# USB_to_UART.net
KiCad netlist of a schematic drawn in Altium Designer
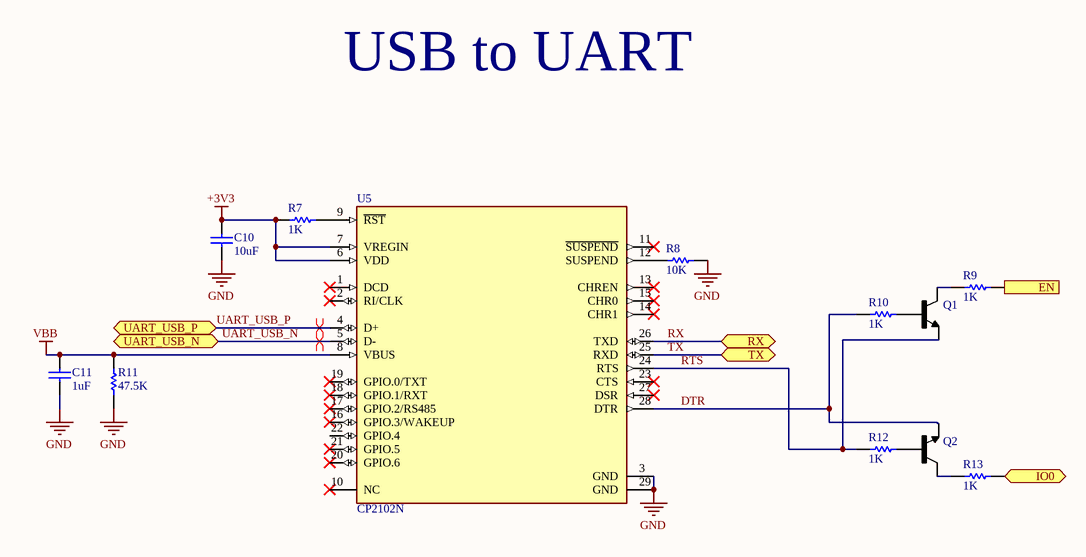
[diagram p0: USB to UART.SchDoc]

(export (version "E")
  (design (tool "Eeschema 10.0.6"))
  (components
    (comp (ref "C10") (value "10uF") (footprint "C0402") (libsource (lib "Schlib1") (part "Cap")))
    (comp (ref "C11") (value "1uF") (footprint "C0402") (libsource (lib "Schlib1") (part "Cap")))
    (comp (ref "Q1") (value "Transistor") (footprint "Transistor") (libsource (lib "") (part "Transistor_1")))
    (comp (ref "Q2")
      (value "Transistor")
      (footprint "Transistor")
      (libsource (lib "Schlib1") (part "Transistor"))
    )
    (comp (ref "R7") (value "1K") (footprint "R0402") (libsource (lib "Schlib1") (part "Res")))
    (comp (ref "R8") (value "10K") (footprint "R0402") (libsource (lib "Schlib1") (part "Res")))
    (comp (ref "R9") (value "1K") (footprint "R0402") (libsource (lib "Schlib1") (part "Res")))
    (comp (ref "R10") (value "1K") (footprint "R0402") (libsource (lib "Schlib1") (part "Res")))
    (comp (ref "R11") (value "47.5K") (footprint "R0402") (libsource (lib "Schlib1") (part "Res")))
    (comp (ref "R12") (value "1K") (footprint "R0402") (libsource (lib "Schlib1") (part "Res")))
    (comp (ref "R13") (value "1K") (footprint "R0402") (libsource (lib "Schlib1") (part "Res")))
    (comp (ref "U5")
      (value "CP2102N")
      (footprint "QFN28")
      (description "USB Bridge, USB to UART USB 2.0 UART Interface 28-QFN (5x5)")
      (libsource (lib "Schlib1") (part "CP2102N"))
    )
  )
  (nets
    (net (code "1") (name "+3V3") (class "Default")
      (node (ref "C10") (pin "02") (pinfunction "-_02") (pintype "passive"))
      (node (ref "R7") (pin "02") (pinfunction "02_02") (pintype "passive"))
      (node (ref "U5") (pin "6") (pinfunction "VDD_6") (pintype "input"))
      (node (ref "U5") (pin "7") (pinfunction "VREGIN_7") (pintype "input"))
    )
    (net (code "2") (name "/DTR") (class "Default")
      (node (ref "Q2") (pin "2") (pinfunction "E_2") (pintype "passive"))
      (node (ref "R10") (pin "02") (pinfunction "02_02") (pintype "passive"))
      (node (ref "U5") (pin "28") (pinfunction "DTR_28") (pintype "output"))
    )
    (net (code "3") (name "/EN") (class "Default")
      (node (ref "R9") (pin "01") (pinfunction "01_01") (pintype "passive"))
    )
    (net (code "4") (name "/IO0") (class "Default")
      (node (ref "R13") (pin "01") (pinfunction "01_01") (pintype "passive"))
    )
    (net (code "5") (name "/RTS") (class "Default")
      (node (ref "Q1") (pin "2") (pinfunction "E_2") (pintype "passive"))
      (node (ref "R12") (pin "02") (pinfunction "02_02") (pintype "passive"))
      (node (ref "U5") (pin "24") (pinfunction "RTS_24") (pintype "output"))
    )
    (net (code "6") (name "/RX") (class "Default")
      (node (ref "U5") (pin "26") (pinfunction "TXD_26") (pintype "bidirectional"))
    )
    (net (code "7") (name "/TX") (class "Default")
      (node (ref "U5") (pin "25") (pinfunction "RXD_25") (pintype "bidirectional"))
    )
    (net (code "8") (name "/UART_USB_N") (class "Default")
      (node (ref "U5") (pin "5") (pinfunction "D-_5") (pintype "bidirectional"))
    )
    (net (code "9") (name "/UART_USB_P") (class "Default")
      (node (ref "U5") (pin "4") (pinfunction "D+_4") (pintype "bidirectional"))
    )
    (net (code "10") (name "GND") (class "Default")
      (node (ref "C10") (pin "01") (pinfunction "+_01") (pintype "passive"))
      (node (ref "C11") (pin "01") (pinfunction "+_01") (pintype "passive"))
      (node (ref "R11") (pin "01") (pinfunction "01_01") (pintype "passive"))
      (node (ref "R8") (pin "01") (pinfunction "01_01") (pintype "passive"))
      (node (ref "U5") (pin "29") (pinfunction "GND_29") (pintype "power_in"))
      (node (ref "U5") (pin "3") (pinfunction "GND_3") (pintype "power_in"))
    )
    (net (code "11") (name "Net-(Q1-B)") (class "Default")
      (node (ref "Q1") (pin "1") (pinfunction "B_1") (pintype "passive"))
      (node (ref "R10") (pin "01") (pinfunction "01_01") (pintype "passive"))
    )
    (net (code "12") (name "Net-(Q1-C)") (class "Default")
      (node (ref "Q1") (pin "3") (pinfunction "C_3") (pintype "passive"))
      (node (ref "R9") (pin "02") (pinfunction "02_02") (pintype "passive"))
    )
    (net (code "13") (name "Net-(Q2-B)") (class "Default")
      (node (ref "Q2") (pin "1") (pinfunction "B_1") (pintype "passive"))
      (node (ref "R12") (pin "01") (pinfunction "01_01") (pintype "passive"))
    )
    (net (code "14") (name "Net-(Q2-C)") (class "Default")
      (node (ref "Q2") (pin "3") (pinfunction "C_3") (pintype "passive"))
      (node (ref "R13") (pin "02") (pinfunction "02_02") (pintype "passive"))
    )
    (net (code "15") (name "Net-(U5-SUSPEND)") (class "Default")
      (node (ref "R8") (pin "02") (pinfunction "02_02") (pintype "passive"))
      (node (ref "U5") (pin "12") (pinfunction "SUSPEND_12") (pintype "output"))
    )
    (net (code "16") (name "Net-(U5-~{RST})") (class "Default")
      (node (ref "R7") (pin "01") (pinfunction "01_01") (pintype "passive"))
      (node (ref "U5") (pin "9") (pinfunction "~{RST}_9") (pintype "input"))
    )
    (net (code "17") (name "VBB") (class "Default")
      (node (ref "C11") (pin "02") (pinfunction "-_02") (pintype "passive"))
      (node (ref "R11") (pin "02") (pinfunction "02_02") (pintype "passive"))
      (node (ref "U5") (pin "8") (pinfunction "VBUS_8") (pintype "input"))
    )
    (net (code "18") (name "unconnected-(U5-CHR0-Pad15)") (class "Default")
      (node (ref "U5") (pin "15") (pinfunction "CHR0_15") (pintype "output+no_connect"))
    )
    (net (code "19") (name "unconnected-(U5-CHR1-Pad14)") (class "Default")
      (node (ref "U5") (pin "14") (pinfunction "CHR1_14") (pintype "output+no_connect"))
    )
    (net (code "20") (name "unconnected-(U5-CHREN-Pad13)") (class "Default")
      (node (ref "U5") (pin "13") (pinfunction "CHREN_13") (pintype "output+no_connect"))
    )
    (net (code "21") (name "unconnected-(U5-CTS-Pad23)") (class "Default")
      (node (ref "U5") (pin "23") (pinfunction "CTS_23") (pintype "input+no_connect"))
    )
    (net (code "22") (name "unconnected-(U5-DCD-Pad1)") (class "Default")
      (node (ref "U5") (pin "1") (pinfunction "DCD_1") (pintype "input+no_connect"))
    )
    (net (code "23") (name "unconnected-(U5-DSR-Pad27)") (class "Default")
      (node (ref "U5") (pin "27") (pinfunction "DSR_27") (pintype "input+no_connect"))
    )
    (net (code "24") (name "unconnected-(U5-GPIO.0{slash}TXT-Pad19)") (class "Default")
      (node (ref "U5") (pin "19") (pinfunction "GPIO.0/TXT_19") (pintype "bidirectional+no_connect"))
    )
    (net (code "25") (name "unconnected-(U5-GPIO.1{slash}RXT-Pad18)") (class "Default")
      (node (ref "U5") (pin "18") (pinfunction "GPIO.1/RXT_18") (pintype "bidirectional+no_connect"))
    )
    (net (code "26") (name "unconnected-(U5-GPIO.2{slash}RS485-Pad17)") (class "Default")
      (node (ref "U5") (pin "17") (pinfunction "GPIO.2/RS485_17") (pintype "bidirectional+no_connect"))
    )
    (net (code "27") (name "unconnected-(U5-GPIO.3{slash}WAKEUP-Pad16)") (class "Default")
      (node (ref "U5") (pin "16") (pinfunction "GPIO.3/WAKEUP_16") (pintype "bidirectional+no_connect"))
    )
    (net (code "28") (name "unconnected-(U5-GPIO.4-Pad22)") (class "Default")
      (node (ref "U5") (pin "22") (pinfunction "GPIO.4_22") (pintype "bidirectional"))
    )
    (net (code "29") (name "unconnected-(U5-GPIO.5-Pad21)") (class "Default")
      (node (ref "U5") (pin "21") (pinfunction "GPIO.5_21") (pintype "bidirectional+no_connect"))
    )
    (net (code "30") (name "unconnected-(U5-GPIO.6-Pad20)") (class "Default")
      (node (ref "U5") (pin "20") (pinfunction "GPIO.6_20") (pintype "bidirectional+no_connect"))
    )
    (net (code "31") (name "unconnected-(U5-NC-Pad10)") (class "Default")
      (node (ref "U5") (pin "10") (pinfunction "NC_10") (pintype "passive+no_connect"))
    )
    (net (code "32") (name "unconnected-(U5-RI{slash}CLK-Pad2)") (class "Default")
      (node (ref "U5") (pin "2") (pinfunction "RI/CLK_2") (pintype "bidirectional+no_connect"))
    )
    (net (code "33") (name "unconnected-(U5-~{SUSPEND}-Pad11)") (class "Default")
      (node (ref "U5") (pin "11") (pinfunction "~{SUSPEND}_11") (pintype "output+no_connect"))
    )
  )
)
